# BTL_RELAY.net
KiCad netlist of a schematic drawn in Altium Designer
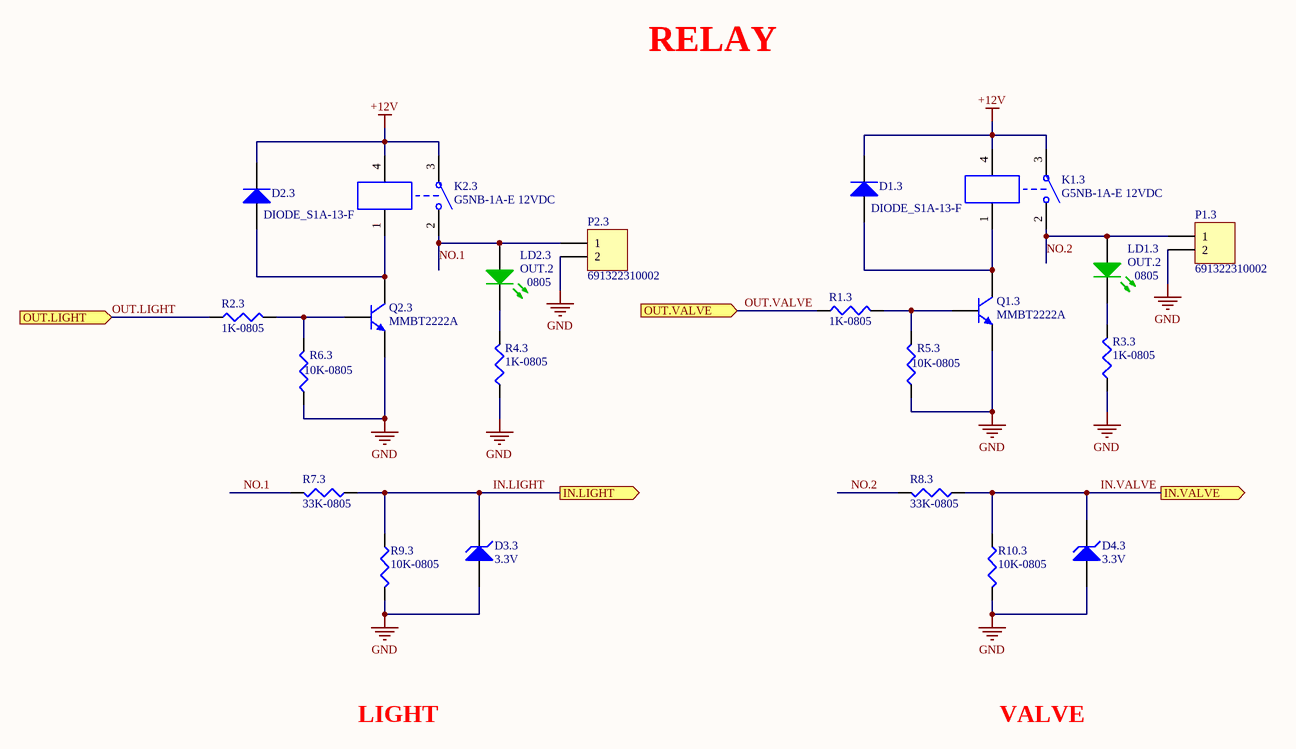
[diagram p0: BTL_RELAY.SchDoc]

(export (version "E")
  (design (tool "Eeschema 10.0.6"))
  (components
    (comp (ref "D1.3")
      (value "DIODE_S1A-13-F")
      (footprint "DO-214AC")
      (description "DIODE GEN PURP 50V 1A SMA")
      (fields
        (field (name "MANUFACTURER") "Diodes Incorporated")
        (field (name "MANUFACTURER PART NUMBER") "S1A-13-F")
      )
      (libsource (lib "Indruino") (part "DIODE_S1A-13-F"))
    )
    (comp (ref "D2.3")
      (value "DIODE_S1A-13-F")
      (footprint "DO-214AC")
      (description "DIODE GEN PURP 50V 1A SMA")
      (fields
        (field (name "MANUFACTURER") "Diodes Incorporated")
        (field (name "MANUFACTURER PART NUMBER") "S1A-13-F")
      )
      (libsource (lib "Indruino") (part "DIODE_S1A-13-F"))
    )
    (comp (ref "D3.3")
      (value "3.3V")
      (footprint "MinhTien_PcbLib:SOD123")
      (description "Zener Diode")
      (fields (field (name "PUBLISHER") "Altium Limited"))
      (libsource (lib "MinhTien_SCHLib") (part "D Zener"))
    )
    (comp (ref "D4.3")
      (value "3.3V")
      (footprint "MinhTien_PcbLib:SOD123")
      (description "Zener Diode")
      (fields (field (name "PUBLISHER") "Altium Limited"))
      (libsource (lib "MinhTien_SCHLib") (part "D Zener"))
    )
    (comp (ref "K1.3")
      (value "G5NB-1A-E 12VDC")
      (footprint "MinhTien_PCBLib:RELAY-G5NB-1A-E 24VDC")
      (description "Relay 24VDC SPST-NO General Purpose / Industrial")
      (fields (field (name "PUBLISHER") "Altium Limited"))
      (libsource (lib "MinhTien_SCHLib") (part "Relay-G5NB-1A-E 24VDC"))
    )
    (comp (ref "K2.3")
      (value "G5NB-1A-E 12VDC")
      (footprint "MinhTien_PCBLib:RELAY-G5NB-1A-E 24VDC")
      (description "Relay 24VDC SPST-NO General Purpose / Industrial")
      (fields (field (name "PUBLISHER") "Altium Limited"))
      (libsource (lib "MinhTien_SCHLib") (part "Relay-G5NB-1A-E 24VDC"))
    )
    (comp (ref "LD1.3")
      (value "OUT.2")
      (footprint "LED_SMD0805_GREEN")
      (description "LED GREEN CLEAR 0805 SMD")
      (fields
        (field (name "MANUFACTURER") "Lite-On Inc.")
        (field (name "MANUFACTURER PART NUMBER") "LTST-C171KGKT")
        (field (name "PACKAGE / CASE") "0805")
      )
      (libsource (lib "Indruino") (part "LED_LTST-C171KGKT"))
    )
    (comp (ref "LD2.3")
      (value "OUT.2")
      (footprint "LED_SMD0805_GREEN")
      (description "LED GREEN CLEAR 0805 SMD")
      (fields
        (field (name "MANUFACTURER") "Lite-On Inc.")
        (field (name "MANUFACTURER PART NUMBER") "LTST-C171KGKT")
        (field (name "PACKAGE / CASE") "0805")
      )
      (libsource (lib "Indruino") (part "LED_LTST-C171KGKT"))
    )
    (comp (ref "P1.3")
      (value "691322310002")
      (footprint "TERMINAL_KF2EDGR_F_1X2_3.81")
      (description "TERM BLOCK HDR 2POS 90DEG 3.81MM")
      (fields (field (name "MANUFACTURER") "Wurth Electronics Inc."))
      (libsource (lib "Indruino") (part "TERMINAL_KF2EDGR_F_1X2_3.81"))
    )
    (comp (ref "P2.3")
      (value "691322310002")
      (footprint "TERMINAL_KF2EDGR_F_1X2_3.81")
      (description "TERM BLOCK HDR 2POS 90DEG 3.81MM")
      (fields (field (name "MANUFACTURER") "Wurth Electronics Inc."))
      (libsource (lib "Indruino") (part "TERMINAL_KF2EDGR_F_1X2_3.81"))
    )
    (comp (ref "Q1.3")
      (value "MMBT2222A")
      (footprint "Indruino:SOT23-3")
      (description "TRANS NPN 40V 1A SOT-23")
      (fields (field (name "MANUFACTURER") "ON Semiconductor") (field (name "BASE PART NUMBER") "MMBT2222"))
      (libsource (lib "Indruino") (part "MMBT2222A"))
    )
    (comp (ref "Q2.3")
      (value "MMBT2222A")
      (footprint "Indruino:SOT23-3")
      (description "TRANS NPN 40V 1A SOT-23")
      (fields (field (name "MANUFACTURER") "ON Semiconductor") (field (name "BASE PART NUMBER") "MMBT2222"))
      (libsource (lib "Indruino") (part "MMBT2222A"))
    )
    (comp (ref "R1.3")
      (value "1K-0805")
      (footprint "RES0805")
      (description "RES SMD 0.0OHM JUMPER 1/8W 0805")
      (fields (field (name "TOLERANCE") "Jumper"))
      (libsource (lib "Indruino") (part "AC0805JR-070RL"))
    )
    (comp (ref "R2.3")
      (value "1K-0805")
      (footprint "RES0805")
      (description "RES SMD 0.0OHM JUMPER 1/8W 0805")
      (fields (field (name "TOLERANCE") "Jumper"))
      (libsource (lib "Indruino") (part "AC0805JR-070RL"))
    )
    (comp (ref "R3.3")
      (value "1K-0805")
      (footprint "RES0805")
      (description "RES SMD 0.0OHM JUMPER 1/8W 0805")
      (fields (field (name "TOLERANCE") "Jumper"))
      (libsource (lib "Indruino") (part "AC0805JR-070RL"))
    )
    (comp (ref "R4.3")
      (value "1K-0805")
      (footprint "RES0805")
      (description "RES SMD 0.0OHM JUMPER 1/8W 0805")
      (fields (field (name "TOLERANCE") "Jumper"))
      (libsource (lib "Indruino") (part "AC0805JR-070RL"))
    )
    (comp (ref "R5.3")
      (value "10K-0805")
      (footprint "RES0805")
      (description "RES SMD 0.0OHM JUMPER 1/8W 0805")
      (fields (field (name "TOLERANCE") "Jumper"))
      (libsource (lib "Indruino") (part "AC0805JR-070RL"))
    )
    (comp (ref "R6.3")
      (value "10K-0805")
      (footprint "RES0805")
      (description "RES SMD 0.0OHM JUMPER 1/8W 0805")
      (fields (field (name "TOLERANCE") "Jumper"))
      (libsource (lib "Indruino") (part "AC0805JR-070RL"))
    )
    (comp (ref "R7.3")
      (value "33K-0805")
      (footprint "RES0805")
      (description "RES SMD 0.0OHM JUMPER 1/8W 0805")
      (fields (field (name "TOLERANCE") "Jumper"))
      (libsource (lib "Indruino") (part "AC0805JR-070RL"))
    )
    (comp (ref "R8.3")
      (value "33K-0805")
      (footprint "RES0805")
      (description "RES SMD 0.0OHM JUMPER 1/8W 0805")
      (fields (field (name "TOLERANCE") "Jumper"))
      (libsource (lib "Indruino") (part "AC0805JR-070RL"))
    )
    (comp (ref "R9.3")
      (value "10K-0805")
      (footprint "RES0805")
      (description "RES SMD 0.0OHM JUMPER 1/8W 0805")
      (fields (field (name "TOLERANCE") "Jumper"))
      (libsource (lib "Indruino") (part "AC0805JR-070RL"))
    )
    (comp (ref "R10.3")
      (value "10K-0805")
      (footprint "RES0805")
      (description "RES SMD 0.0OHM JUMPER 1/8W 0805")
      (fields (field (name "TOLERANCE") "Jumper"))
      (libsource (lib "Indruino") (part "AC0805JR-070RL"))
    )
  )
  (nets
    (net (code "1") (name "+12V") (class "Default")
      (node (ref "D1.3") (pin "2") (pinfunction "K_2") (pintype "passive"))
      (node (ref "D2.3") (pin "2") (pinfunction "K_2") (pintype "passive"))
      (node (ref "K1.3") (pin "3") (pinfunction "NO_3") (pintype "passive"))
      (node (ref "K1.3") (pin "4") (pintype "passive"))
      (node (ref "K2.3") (pin "3") (pinfunction "NO_3") (pintype "passive"))
      (node (ref "K2.3") (pin "4") (pintype "passive"))
    )
    (net (code "2") (name "/IN.LIGHT") (class "Default")
      (node (ref "D3.3") (pin "2") (pinfunction "K_2") (pintype "passive"))
      (node (ref "R7.3") (pin "1") (pinfunction "1_1") (pintype "passive"))
      (node (ref "R9.3") (pin "1") (pinfunction "1_1") (pintype "passive"))
    )
    (net (code "3") (name "/IN.VALVE") (class "Default")
      (node (ref "D4.3") (pin "2") (pinfunction "K_2") (pintype "passive"))
      (node (ref "R10.3") (pin "1") (pinfunction "1_1") (pintype "passive"))
      (node (ref "R8.3") (pin "1") (pinfunction "1_1") (pintype "passive"))
    )
    (net (code "4") (name "/NO.1") (class "Default")
      (node (ref "K2.3") (pin "2") (pinfunction "NC_2") (pintype "passive"))
      (node (ref "LD2.3") (pin "1") (pinfunction "A_1") (pintype "passive"))
      (node (ref "P2.3") (pin "1") (pinfunction "1_1") (pintype "passive"))
      (node (ref "R7.3") (pin "2") (pinfunction "2_2") (pintype "passive"))
    )
    (net (code "5") (name "/NO.2") (class "Default")
      (node (ref "K1.3") (pin "2") (pinfunction "NC_2") (pintype "passive"))
      (node (ref "LD1.3") (pin "1") (pinfunction "A_1") (pintype "passive"))
      (node (ref "P1.3") (pin "1") (pinfunction "1_1") (pintype "passive"))
      (node (ref "R8.3") (pin "2") (pinfunction "2_2") (pintype "passive"))
    )
    (net (code "6") (name "/OUT.LIGHT") (class "Default")
      (node (ref "R2.3") (pin "1") (pinfunction "1_1") (pintype "passive"))
    )
    (net (code "7") (name "/OUT.VALVE") (class "Default")
      (node (ref "R1.3") (pin "1") (pinfunction "1_1") (pintype "passive"))
    )
    (net (code "8") (name "GND") (class "Default")
      (node (ref "D3.3") (pin "1") (pinfunction "A_1") (pintype "passive"))
      (node (ref "D4.3") (pin "1") (pinfunction "A_1") (pintype "passive"))
      (node (ref "P1.3") (pin "2") (pinfunction "2_2") (pintype "passive"))
      (node (ref "P2.3") (pin "2") (pinfunction "2_2") (pintype "passive"))
      (node (ref "Q1.3") (pin "2") (pinfunction "E_2") (pintype "passive"))
      (node (ref "Q2.3") (pin "2") (pinfunction "E_2") (pintype "passive"))
      (node (ref "R10.3") (pin "2") (pinfunction "2_2") (pintype "passive"))
      (node (ref "R3.3") (pin "1") (pinfunction "1_1") (pintype "passive"))
      (node (ref "R4.3") (pin "1") (pinfunction "1_1") (pintype "passive"))
      (node (ref "R5.3") (pin "1") (pinfunction "1_1") (pintype "passive"))
      (node (ref "R6.3") (pin "1") (pinfunction "1_1") (pintype "passive"))
      (node (ref "R9.3") (pin "2") (pinfunction "2_2") (pintype "passive"))
    )
    (net (code "9") (name "Net-(D1.3-A)") (class "Default")
      (node (ref "D1.3") (pin "1") (pinfunction "A_1") (pintype "passive"))
      (node (ref "K1.3") (pin "1") (pinfunction "COM_1") (pintype "passive"))
      (node (ref "Q1.3") (pin "3") (pinfunction "C_3") (pintype "passive"))
    )
    (net (code "10") (name "Net-(D2.3-A)") (class "Default")
      (node (ref "D2.3") (pin "1") (pinfunction "A_1") (pintype "passive"))
      (node (ref "K2.3") (pin "1") (pinfunction "COM_1") (pintype "passive"))
      (node (ref "Q2.3") (pin "3") (pinfunction "C_3") (pintype "passive"))
    )
    (net (code "11") (name "Net-(LD1.3-K)") (class "Default")
      (node (ref "LD1.3") (pin "2") (pinfunction "K_2") (pintype "passive"))
      (node (ref "R3.3") (pin "2") (pinfunction "2_2") (pintype "passive"))
    )
    (net (code "12") (name "Net-(LD2.3-K)") (class "Default")
      (node (ref "LD2.3") (pin "2") (pinfunction "K_2") (pintype "passive"))
      (node (ref "R4.3") (pin "2") (pinfunction "2_2") (pintype "passive"))
    )
    (net (code "13") (name "Net-(Q1.3-B)") (class "Default")
      (node (ref "Q1.3") (pin "1") (pinfunction "B_1") (pintype "passive"))
      (node (ref "R1.3") (pin "2") (pinfunction "2_2") (pintype "passive"))
      (node (ref "R5.3") (pin "2") (pinfunction "2_2") (pintype "passive"))
    )
    (net (code "14") (name "Net-(Q2.3-B)") (class "Default")
      (node (ref "Q2.3") (pin "1") (pinfunction "B_1") (pintype "passive"))
      (node (ref "R2.3") (pin "2") (pinfunction "2_2") (pintype "passive"))
      (node (ref "R6.3") (pin "2") (pinfunction "2_2") (pintype "passive"))
    )
  )
)
